# dcdc_wide_3v3.net
KiCad netlist of a schematic drawn in Altium Designer
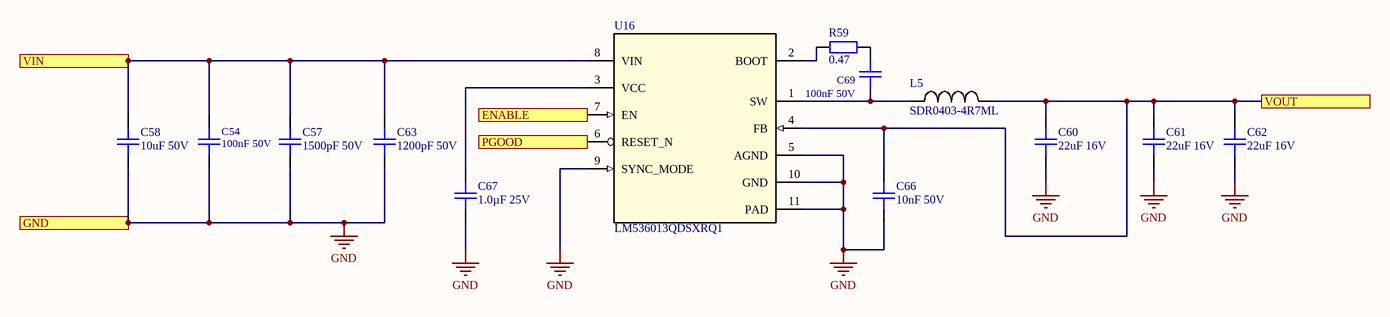
[diagram p0: dcdc_wide_3v3.SchDoc]

(export (version "E")
  (design (tool "Eeschema 10.0.6"))
  (components
    (comp (ref "C54")
      (value "100nF 50V")
      (footprint "0805C")
      (description "Ceramic, 100nF, ±20%, 50V, X7R, –55 to 125°C, 0805 (2012),RoHS, Automotive")
      (fields (field (name "TOLERANCE") "±10%") (field (name "MANUFACTURER") "Murata"))
      (libsource (lib "master-010106") (part "gen_C_ceramic_100n_50V_X7R_0805"))
    )
    (comp (ref "C57")
      (value "1500pF 50V")
      (footprint "0402C")
      (description "Ceramic, 390pF, ±5%, 25V, C0G, 25 to 125°C, 0402 (1005),RoHS, Automotive")
      (fields (field (name "TOLERANCE") "±5%") (field (name "MANUFACTURER") "Murata"))
      (libsource (lib "master-010106") (part "gen_C_ceramic_390p_25V_C0G_0402"))
    )
    (comp (ref "C58")
      (value "10uF 50V")
      (footprint "CAPC3225X279X50LL20T25")
      (description "Ceramic, 10uF, 50 V, -55 to 125 degC, 2-Pin SMD (1210), RoHS, Tape and Reel")
      (fields (field (name "TOLERANCE") "±10%") (field (name "MANUFACTURER") "AVX"))
      (libsource (lib "master-010106") (part "gen_C_ceramic_10u_50V_X7R_1210"))
    )
    (comp (ref "C60")
      (value "22uF 16V")
      (footprint "1210C")
      (description "Ceramic, 22uF, 16 V, -55 to 125 degC, 2-Pin SMD (1210), RoHS, Tape and Reel")
      (fields (field (name "TOLERANCE") "±10%") (field (name "MANUFACTURER") "AVX"))
      (libsource (lib "master-010106") (part "gen_C_ceramic_22u_16V_X7R_1210"))
    )
    (comp (ref "C61")
      (value "22uF 16V")
      (footprint "1210C")
      (description "Ceramic, 22uF, 16 V, -55 to 125 degC, 2-Pin SMD (1210), RoHS, Tape and Reel")
      (fields (field (name "TOLERANCE") "±10%") (field (name "MANUFACTURER") "AVX"))
      (libsource (lib "master-010106") (part "gen_C_ceramic_22u_16V_X7R_1210"))
    )
    (comp (ref "C62")
      (value "22uF 16V")
      (footprint "1210C")
      (description "Ceramic, 22uF, 16 V, -55 to 125 degC, 2-Pin SMD (1210), RoHS, Tape and Reel")
      (fields (field (name "TOLERANCE") "±10%") (field (name "MANUFACTURER") "AVX"))
      (libsource (lib "master-010106") (part "gen_C_ceramic_22u_16V_X7R_1210"))
    )
    (comp (ref "C63")
      (value "1200pF 50V")
      (footprint "0402C")
      (description "Ceramic, 390pF, ±5%, 50V, C0G, 25 to 125°C, 0402 (1005),RoHS, Automotive")
      (fields (field (name "TOLERANCE") "±5%") (field (name "MANUFACTURER") "Murata"))
      (libsource (lib "master-010106") (part "gen_C_ceramic_390p_25V_C0G_0402"))
    )
    (comp (ref "C66")
      (value "10nF 50V")
      (footprint "0402C")
      (description "Ceramic, 10nF, ±10%, 50V, X7R, –55 to 125°C, 0402 (1005),RoHS, Automotive")
      (fields (field (name "PART NUMBER") "GRT155R71H104KE01"))
      (libsource (lib "master-010106") (part "gen_C_ceramic_10n_50V_X7R_0402"))
    )
    (comp (ref "C67")
      (value "1.0µF 25V")
      (footprint "0603C")
      (description "Ceramic, 1.0µF, ±10%, 25V, X7R, –55 to 125°C, 0603 (1608),RoHS, Automotive")
      (fields (field (name "PART NUMBER") "GCJ188R71E105KA01") (field (name "TOLERANCE") "±10%"))
      (libsource (lib "master-010106") (part "gen_C_ceramic_1u_25V_X7R_0603"))
    )
    (comp (ref "C69")
      (value "100nF 50V")
      (footprint "0805C")
      (description "Ceramic, 100nF, ±20%, 50V, X7R, –55 to 125°C, 0805 (2012),RoHS, Automotive")
      (fields (field (name "PART NUMBER") "GCJ188R71H104KA12") (field (name "TOLERANCE") "±10%"))
      (libsource (lib "master-010106") (part "gen_C_ceramic_100n_50V_X7R_0805"))
    )
    (comp (ref "L5")
      (value "SDR0403-4R7ML")
      (footprint "SDR0403")
      (description "4.7uH")
      (libsource (lib "ti-import") (part "SDR0403-4R7ML"))
    )
    (comp (ref "R59")
      (value "0.47")
      (footprint "0402R")
      (description "SMD Resistor 0R47 0402")
      (fields (field (name "PART NUMBER") "gen_R_0R47_0402"))
      (libsource (lib "master-010106") (part "gen_R_0R_0402"))
    )
    (comp (ref "U16")
      (value "LM536013QDSXRQ1")
      (footprint "DSX0010A")
      (description "Imported")
      (fields (field (name "MANUFACTURER") "Texas Instruments"))
      (libsource (lib "ti-import") (part "LM536013QDSXRQ1"))
    )
  )
  (nets
    (net (code "1") (name "/ENABLE") (class "Default")
      (node (ref "U16") (pin "7") (pinfunction "EN_7") (pintype "input"))
    )
    (net (code "2") (name "/PGOOD") (class "Default")
      (node (ref "U16") (pin "6") (pinfunction "RESET_N_6") (pintype "open_collector"))
    )
    (net (code "3") (name "/VIN") (class "Default")
      (node (ref "C54") (pin "2") (pinfunction "2_2") (pintype "passive"))
      (node (ref "C57") (pin "2") (pinfunction "2_2") (pintype "passive"))
      (node (ref "C58") (pin "2") (pinfunction "2_2") (pintype "passive"))
      (node (ref "C63") (pin "2") (pinfunction "2_2") (pintype "passive"))
      (node (ref "U16") (pin "8") (pinfunction "VIN_8") (pintype "power_in"))
    )
    (net (code "4") (name "/VOUT") (class "Default")
      (node (ref "C60") (pin "2") (pinfunction "2_2") (pintype "passive"))
      (node (ref "C61") (pin "2") (pinfunction "2_2") (pintype "passive"))
      (node (ref "C62") (pin "2") (pinfunction "2_2") (pintype "passive"))
      (node (ref "C66") (pin "2") (pinfunction "2_2") (pintype "passive"))
      (node (ref "L5") (pin "2") (pinfunction "2_2") (pintype "passive"))
      (node (ref "U16") (pin "4") (pinfunction "FB_4") (pintype "input"))
    )
    (net (code "5") (name "GND") (class "Default")
      (node (ref "C54") (pin "1") (pinfunction "1_1") (pintype "passive"))
      (node (ref "C57") (pin "1") (pinfunction "1_1") (pintype "passive"))
      (node (ref "C58") (pin "1") (pinfunction "1_1") (pintype "passive"))
      (node (ref "C60") (pin "1") (pinfunction "1_1") (pintype "passive"))
      (node (ref "C61") (pin "1") (pinfunction "1_1") (pintype "passive"))
      (node (ref "C62") (pin "1") (pinfunction "1_1") (pintype "passive"))
      (node (ref "C63") (pin "1") (pinfunction "1_1") (pintype "passive"))
      (node (ref "C66") (pin "1") (pinfunction "1_1") (pintype "passive"))
      (node (ref "C67") (pin "1") (pinfunction "1_1") (pintype "passive"))
      (node (ref "U16") (pin "10") (pinfunction "GND_10") (pintype "power_in"))
      (node (ref "U16") (pin "11") (pinfunction "PAD_11") (pintype "power_in"))
      (node (ref "U16") (pin "5") (pinfunction "AGND_5") (pintype "power_in"))
      (node (ref "U16") (pin "9") (pinfunction "SYNC_MODE_9") (pintype "input"))
    )
    (net (code "6") (name "Net-(C69-Pad2)") (class "Default")
      (node (ref "C69") (pin "2") (pinfunction "2_2") (pintype "passive"))
      (node (ref "R59") (pin "2") (pinfunction "2_2") (pintype "passive"))
    )
    (net (code "7") (name "Net-(U16-BOOT)") (class "Default")
      (node (ref "R59") (pin "1") (pinfunction "1_1") (pintype "passive"))
      (node (ref "U16") (pin "2") (pinfunction "BOOT_2") (pintype "power_in"))
    )
    (net (code "8") (name "Net-(U16-SW)") (class "Default")
      (node (ref "C69") (pin "1") (pinfunction "1_1") (pintype "passive"))
      (node (ref "L5") (pin "1") (pinfunction "1_1") (pintype "passive"))
      (node (ref "U16") (pin "1") (pinfunction "SW_1") (pintype "power_in"))
    )
    (net (code "9") (name "Net-(U16-VCC)") (class "Default")
      (node (ref "C67") (pin "2") (pinfunction "2_2") (pintype "passive"))
      (node (ref "U16") (pin "3") (pinfunction "VCC_3") (pintype "power_in"))
    )
  )
)
